# harp_rfid_reader_v1_0.net
KiCad netlist of a schematic drawn in EAGLE
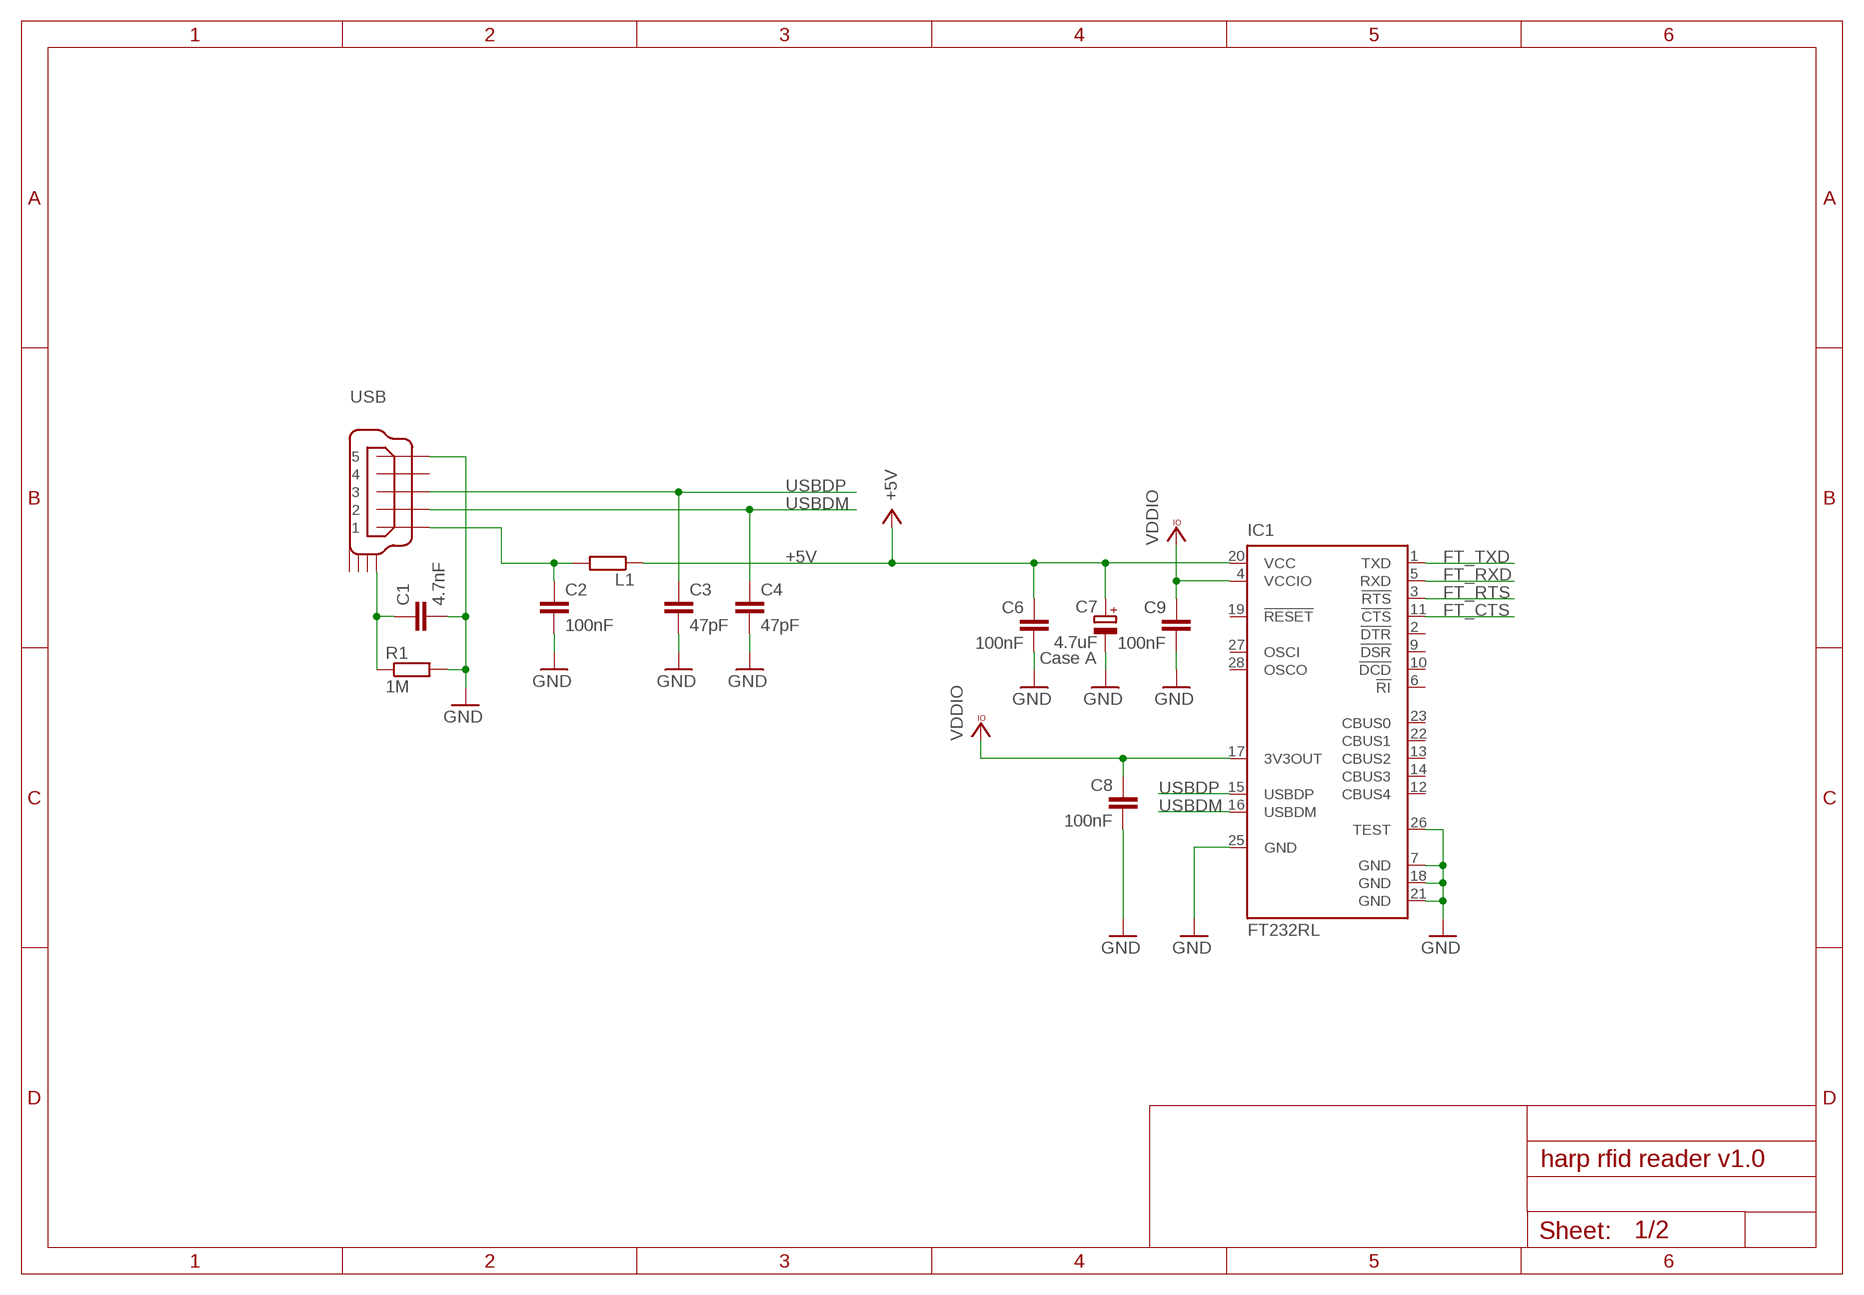
[diagram p0: schematic, sheet 1]
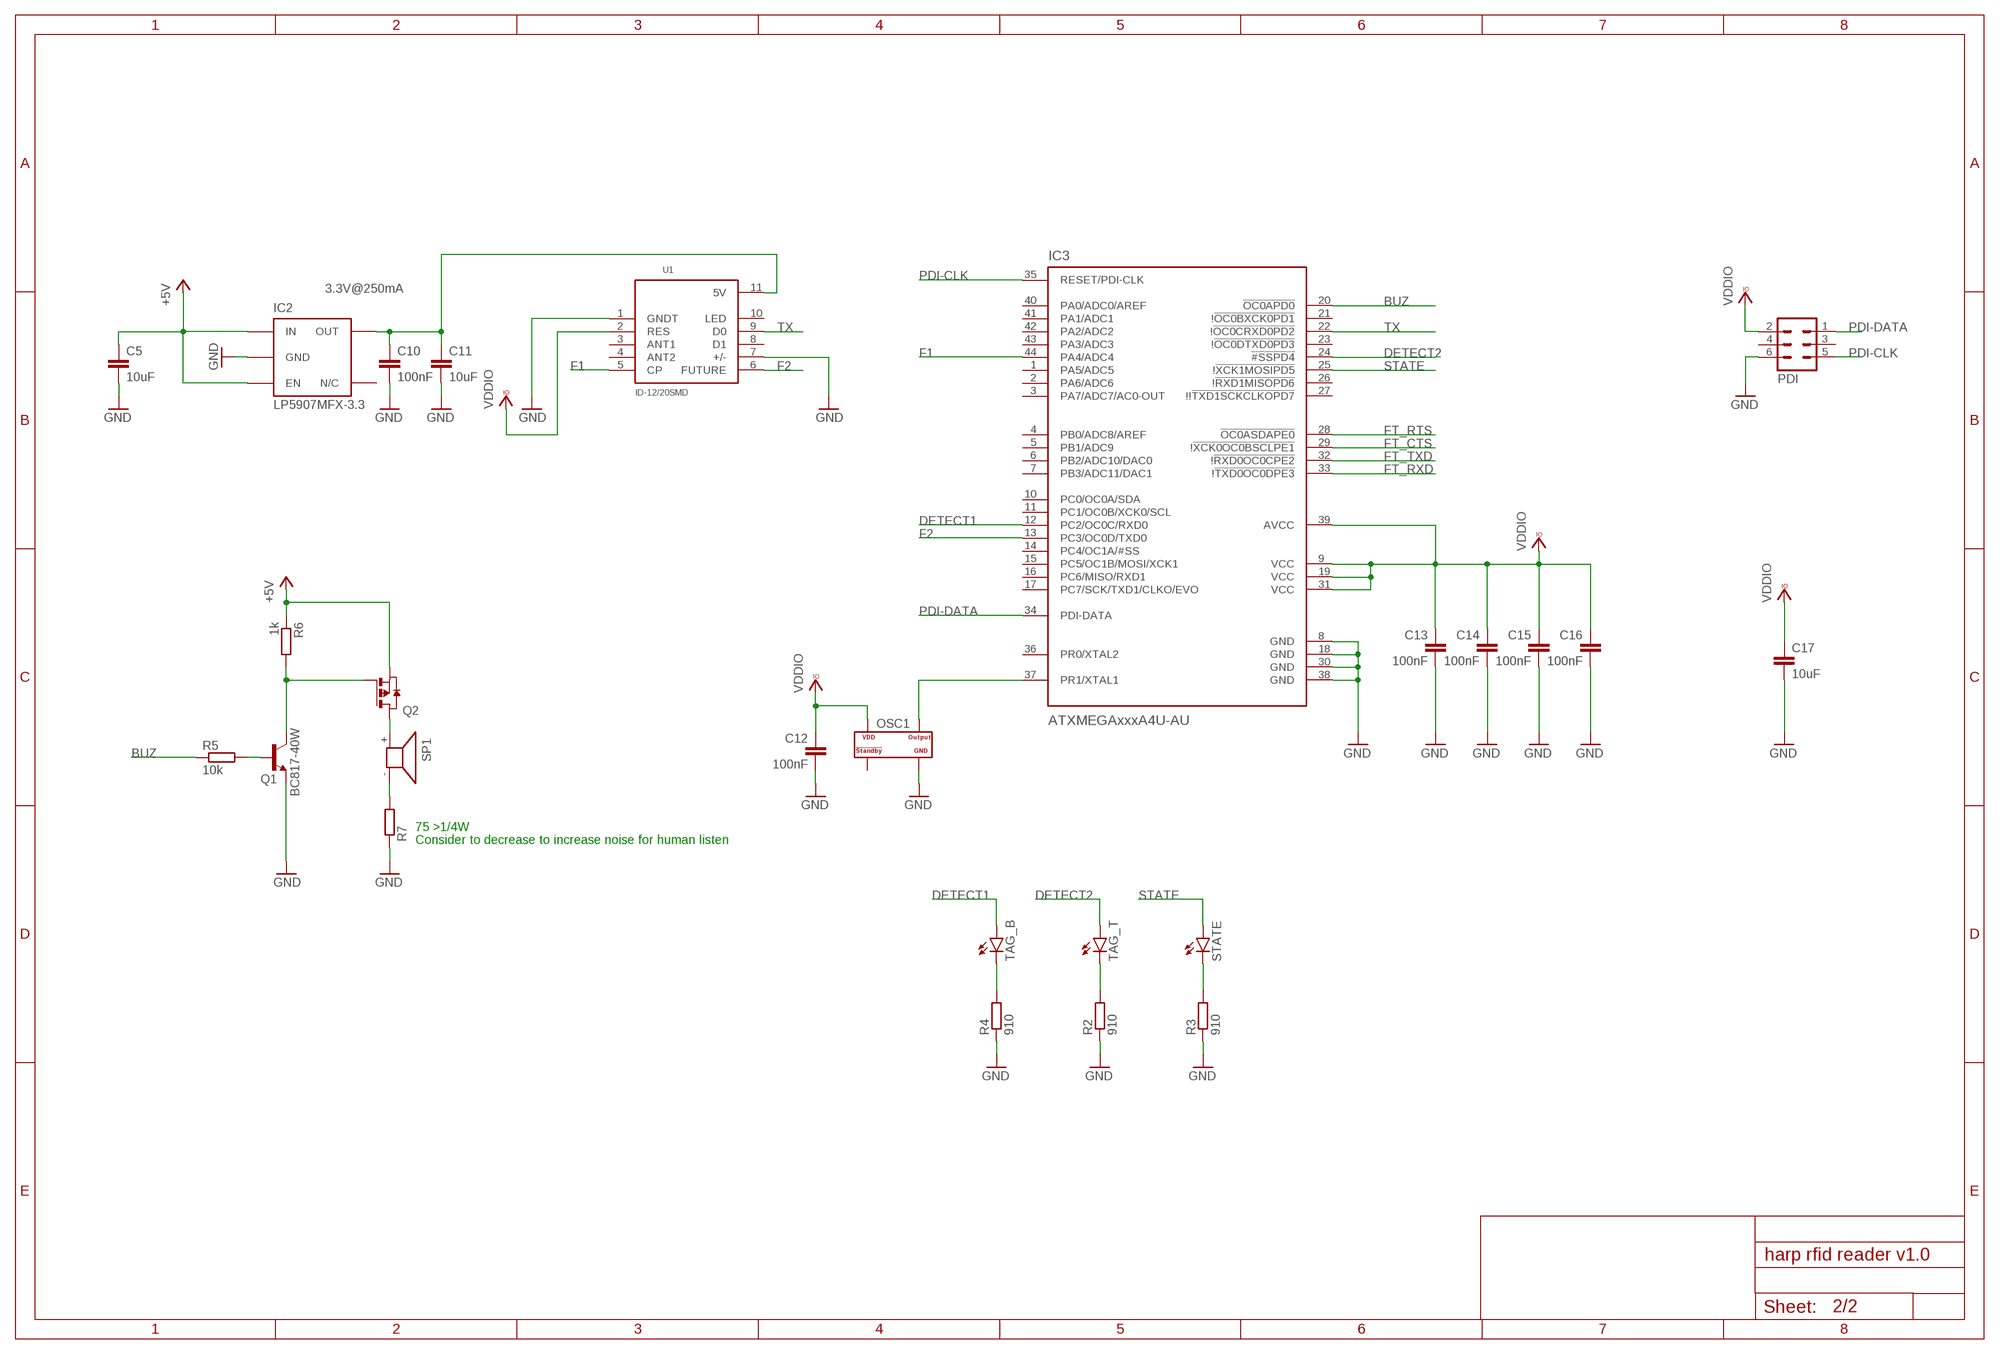
[diagram p1: schematic, sheet 2]

(export (version "E")
  (design (tool "Eeschema 10.0.6"))
  (components
    (comp (ref "C5")
      (value "10uF")
      (footprint "eagle-import:C0603")
      (libsource (lib "eagle-import") (part "C-EUC0603"))
    )
    (comp (ref "C10")
      (value "100nF")
      (footprint "eagle-import:C0402")
      (libsource (lib "eagle-import") (part "C-EUC0402"))
    )
    (comp (ref "C11")
      (value "10uF")
      (footprint "eagle-import:C0603")
      (libsource (lib "eagle-import") (part "C-EUC0603"))
    )
    (comp (ref "C12")
      (value "100nF")
      (footprint "eagle-import:C0402")
      (libsource (lib "eagle-import") (part "C-EUC0402"))
    )
    (comp (ref "C13")
      (value "100nF")
      (footprint "eagle-import:C0402")
      (libsource (lib "eagle-import") (part "C-EUC0402"))
    )
    (comp (ref "C14")
      (value "100nF")
      (footprint "eagle-import:C0402")
      (libsource (lib "eagle-import") (part "C-EUC0402"))
    )
    (comp (ref "C15")
      (value "100nF")
      (footprint "eagle-import:C0402")
      (libsource (lib "eagle-import") (part "C-EUC0402"))
    )
    (comp (ref "C16")
      (value "100nF")
      (footprint "eagle-import:C0402")
      (libsource (lib "eagle-import") (part "C-EUC0402"))
    )
    (comp (ref "C17")
      (value "10uF")
      (footprint "eagle-import:C0603")
      (libsource (lib "eagle-import") (part "C-EUC0603"))
    )
    (comp (ref "IC2")
      (value "LP5907MFX-3.3")
      (footprint "eagle-import:TSOT23-5")
      (libsource (lib "eagle-import") (part "TLV700XX"))
    )
    (comp (ref "IC3")
      (value "ATXMEGAxxxA4U-AU")
      (footprint "eagle-import:QFP80P1200X1200X120-44N")
      (libsource (lib "eagle-import") (part "AT-XMEGA-XXA4-AU"))
    )
    (comp (ref "OSC1")
      (value "CNP-MISCELLANEOUS_OSCILLATOR")
      (footprint "eagle-import:CNP-MISCELLANEOUS_OSCILLATOR_3.2X2.5")
      (libsource (lib "eagle-import") (part "CNP-MISCELLANEOUS_OSCILLATOR"))
    )
    (comp (ref "PDI")
      (value "MA03-2")
      (footprint "eagle-import:MA03-2")
      (libsource (lib "eagle-import") (part "MA03-2"))
    )
    (comp (ref "Q1")
      (value "BC817-40W")
      (footprint "eagle-import:SOT323-BEC")
      (libsource (lib "eagle-import") (part "BC817"))
    )
    (comp (ref "Q2")
      (value "PMOSSOT223")
      (footprint "eagle-import:SOT223")
      (libsource (lib "eagle-import") (part "PMOSSOT223"))
    )
    (comp (ref "R2")
      (value "910")
      (footprint "eagle-import:R0402")
      (libsource (lib "eagle-import") (part "rcl_334_R-EU_R0402"))
    )
    (comp (ref "R3")
      (value "910")
      (footprint "eagle-import:R0402")
      (libsource (lib "eagle-import") (part "rcl_334_R-EU_R0402"))
    )
    (comp (ref "R4")
      (value "910")
      (footprint "eagle-import:R0402")
      (libsource (lib "eagle-import") (part "rcl_334_R-EU_R0402"))
    )
    (comp (ref "R5")
      (value "10k")
      (footprint "eagle-import:R0402")
      (libsource (lib "eagle-import") (part "R-EU_R0402"))
    )
    (comp (ref "R6")
      (value "1k")
      (footprint "eagle-import:R0402")
      (libsource (lib "eagle-import") (part "R-EU_R0402"))
    )
    (comp (ref "R7")
      (value "75 >1/4W")
      (footprint "eagle-import:R0402")
      (libsource (lib "eagle-import") (part "R-EU_R0402"))
    )
    (comp (ref "SP1")
      (value "BUZZER-COIL_SMT-0540-S-R")
      (footprint "eagle-import:BUZZER-COIL_SMT-0540-S-R")
      (libsource (lib "eagle-import") (part "BUZZER-COIL_SMT-0540-S-R"))
    )
    (comp (ref "STATE")
      (value "LEDCHIP-LED0603")
      (footprint "eagle-import:CHIP-LED0603")
      (libsource (lib "eagle-import") (part "LEDCHIP-LED0603"))
    )
    (comp (ref "TAG_B")
      (value "LEDCHIP-LED0603")
      (footprint "eagle-import:CHIP-LED0603")
      (libsource (lib "eagle-import") (part "LEDCHIP-LED0603"))
    )
    (comp (ref "TAG_T")
      (value "LEDCHIP-LED0603")
      (footprint "eagle-import:CHIP-LED0603")
      (libsource (lib "eagle-import") (part "LEDCHIP-LED0603"))
    )
    (comp (ref "U1")
      (value "ID-12/20SMD")
      (footprint "eagle-import:ID-12_SMD")
      (libsource (lib "eagle-import") (part "ID-12/20SMD"))
    )
    (comp (ref "C1")
      (value "4.7nF")
      (footprint "eagle-import:C0402")
      (libsource (lib "eagle-import") (part "C-EUC0402"))
    )
    (comp (ref "C2")
      (value "100nF")
      (footprint "eagle-import:C0402")
      (libsource (lib "eagle-import") (part "C-EUC0402"))
    )
    (comp (ref "C3")
      (value "47pF")
      (footprint "eagle-import:C0402")
      (libsource (lib "eagle-import") (part "C-EUC0402"))
    )
    (comp (ref "C4")
      (value "47pF")
      (footprint "eagle-import:C0402")
      (libsource (lib "eagle-import") (part "C-EUC0402"))
    )
    (comp (ref "C6")
      (value "100nF")
      (footprint "eagle-import:C0402")
      (libsource (lib "eagle-import") (part "C-EUC0402"))
    )
    (comp (ref "C7")
      (value "4.7uF")
      (footprint "eagle-import:A_3216-18W")
      (libsource (lib "eagle-import") (part "CPOL-EUA/3216-18W"))
    )
    (comp (ref "C8")
      (value "100nF")
      (footprint "eagle-import:C0402")
      (libsource (lib "eagle-import") (part "C-EUC0402"))
    )
    (comp (ref "C9")
      (value "100nF")
      (footprint "eagle-import:C0402")
      (libsource (lib "eagle-import") (part "C-EUC0402"))
    )
    (comp (ref "IC1")
      (value "FT232RL")
      (footprint "eagle-import:SSOP28")
      (libsource (lib "eagle-import") (part "FT232RL"))
    )
    (comp (ref "L1")
      (value "???")
      (footprint "eagle-import:R0805")
      (libsource (lib "eagle-import") (part "R-EU_R0805"))
    )
    (comp (ref "R1")
      (value "1M")
      (footprint "eagle-import:R0402")
      (libsource (lib "eagle-import") (part "R-EU_R0402"))
    )
    (comp (ref "USB")
      (value "USB_MINI_B")
      (footprint "eagle-import:240-0002-1")
      (libsource (lib "eagle-import") (part "USB_MINI_B"))
    )
  )
  (nets
    (net (code "1") (name "+5V") (class "Default")
      (node (ref "C5") (pin "1") (pinfunction "1_1") (pintype "passive"))
      (node (ref "C6") (pin "1") (pinfunction "1_1") (pintype "passive"))
      (node (ref "C7") (pin "+") (pinfunction "+_+") (pintype "passive"))
      (node (ref "IC1") (pin "20") (pinfunction "VCC_20") (pintype "power_in"))
      (node (ref "IC2") (pin "1") (pinfunction "IN_1") (pintype "bidirectional"))
      (node (ref "IC2") (pin "3") (pinfunction "EN_3") (pintype "bidirectional"))
      (node (ref "L1") (pin "1") (pinfunction "1_1") (pintype "passive"))
      (node (ref "Q2") (pin "3") (pinfunction "S_3") (pintype "passive"))
      (node (ref "R6") (pin "1") (pinfunction "1_1") (pintype "passive"))
    )
    (net (code "2") (name "BUZ") (class "Default")
      (node (ref "IC3") (pin "20") (pinfunction "~{OC0APD0}_20") (pintype "bidirectional"))
      (node (ref "R5") (pin "1") (pinfunction "1_1") (pintype "passive"))
    )
    (net (code "3") (name "DETECT1") (class "Default")
      (node (ref "IC3") (pin "12") (pinfunction "PC2/OC0C/RXD0_12") (pintype "bidirectional"))
      (node (ref "TAG_B") (pin "A") (pinfunction "A_A") (pintype "passive"))
    )
    (net (code "4") (name "DETECT2") (class "Default")
      (node (ref "IC3") (pin "24") (pinfunction "~{#SSPD4}_24") (pintype "bidirectional"))
      (node (ref "TAG_T") (pin "A") (pinfunction "A_A") (pintype "passive"))
    )
    (net (code "5") (name "F1") (class "Default")
      (node (ref "IC3") (pin "44") (pinfunction "PA4/ADC4_44") (pintype "bidirectional"))
      (node (ref "U1") (pin "5") (pinfunction "CP_5") (pintype "bidirectional"))
    )
    (net (code "6") (name "F2") (class "Default")
      (node (ref "IC3") (pin "13") (pinfunction "PC3/OC0D/TXD0_13") (pintype "bidirectional"))
      (node (ref "U1") (pin "6") (pinfunction "FUTURE_6") (pintype "bidirectional"))
    )
    (net (code "7") (name "FT_CTS") (class "Default")
      (node (ref "IC1") (pin "11") (pinfunction "~{CTS}_11") (pintype "input"))
      (node (ref "IC3") (pin "29") (pinfunction "~XCK0OC0BSCLPE1_29") (pintype "bidirectional"))
    )
    (net (code "8") (name "FT_RTS") (class "Default")
      (node (ref "IC1") (pin "3") (pinfunction "~{RTS}_3") (pintype "output"))
      (node (ref "IC3") (pin "28") (pinfunction "~{OC0ASDAPE0}_28") (pintype "bidirectional"))
    )
    (net (code "9") (name "FT_RXD") (class "Default")
      (node (ref "IC1") (pin "5") (pinfunction "RXD_5") (pintype "input"))
      (node (ref "IC3") (pin "33") (pinfunction "~TXD0OC0DPE3_33") (pintype "bidirectional"))
    )
    (net (code "10") (name "FT_TXD") (class "Default")
      (node (ref "IC1") (pin "1") (pinfunction "TXD_1") (pintype "output"))
      (node (ref "IC3") (pin "32") (pinfunction "~RXD0OC0CPE2_32") (pintype "bidirectional"))
    )
    (net (code "11") (name "GND") (class "Default")
      (node (ref "C1") (pin "2") (pinfunction "2_2") (pintype "passive"))
      (node (ref "C10") (pin "2") (pinfunction "2_2") (pintype "passive"))
      (node (ref "C11") (pin "2") (pinfunction "2_2") (pintype "passive"))
      (node (ref "C12") (pin "2") (pinfunction "2_2") (pintype "passive"))
      (node (ref "C13") (pin "2") (pinfunction "2_2") (pintype "passive"))
      (node (ref "C14") (pin "2") (pinfunction "2_2") (pintype "passive"))
      (node (ref "C15") (pin "2") (pinfunction "2_2") (pintype "passive"))
      (node (ref "C16") (pin "2") (pinfunction "2_2") (pintype "passive"))
      (node (ref "C17") (pin "2") (pinfunction "2_2") (pintype "passive"))
      (node (ref "C2") (pin "2") (pinfunction "2_2") (pintype "passive"))
      (node (ref "C3") (pin "2") (pinfunction "2_2") (pintype "passive"))
      (node (ref "C4") (pin "2") (pinfunction "2_2") (pintype "passive"))
      (node (ref "C5") (pin "2") (pinfunction "2_2") (pintype "passive"))
      (node (ref "C6") (pin "2") (pinfunction "2_2") (pintype "passive"))
      (node (ref "C7") (pin "-") (pinfunction "-_-") (pintype "passive"))
      (node (ref "C8") (pin "2") (pinfunction "2_2") (pintype "passive"))
      (node (ref "C9") (pin "2") (pinfunction "2_2") (pintype "passive"))
      (node (ref "IC1") (pin "18") (pinfunction "GND_18") (pintype "power_in"))
      (node (ref "IC1") (pin "21") (pinfunction "GND_21") (pintype "power_in"))
      (node (ref "IC1") (pin "25") (pinfunction "GND_25") (pintype "power_in"))
      (node (ref "IC1") (pin "26") (pinfunction "TEST_26") (pintype "input"))
      (node (ref "IC1") (pin "7") (pinfunction "GND_7") (pintype "power_in"))
      (node (ref "IC2") (pin "2") (pinfunction "GND_2") (pintype "bidirectional"))
      (node (ref "IC3") (pin "18") (pinfunction "GND_18") (pintype "power_in"))
      (node (ref "IC3") (pin "30") (pinfunction "GND_30") (pintype "power_in"))
      (node (ref "IC3") (pin "38") (pinfunction "GND_38") (pintype "power_in"))
      (node (ref "IC3") (pin "8") (pinfunction "GND_8") (pintype "power_in"))
      (node (ref "OSC1") (pin "P$2") (pinfunction "GND_P$2") (pintype "passive"))
      (node (ref "PDI") (pin "6") (pinfunction "6_6") (pintype "passive"))
      (node (ref "Q1") (pin "E") (pinfunction "E_E") (pintype "passive"))
      (node (ref "R1") (pin "2") (pinfunction "2_2") (pintype "passive"))
      (node (ref "R2") (pin "1") (pinfunction "1_1") (pintype "passive"))
      (node (ref "R3") (pin "1") (pinfunction "1_1") (pintype "passive"))
      (node (ref "R4") (pin "1") (pinfunction "1_1") (pintype "passive"))
      (node (ref "R7") (pin "1") (pinfunction "1_1") (pintype "passive"))
      (node (ref "U1") (pin "1") (pinfunction "GNDT_1") (pintype "bidirectional"))
      (node (ref "U1") (pin "7") (pinfunction "+/-_7") (pintype "bidirectional"))
      (node (ref "USB") (pin "P$5") (pinfunction "5_P$5") (pintype "bidirectional"))
    )
    (net (code "12") (name "Net-(IC2-OUT)") (class "Default")
      (node (ref "C10") (pin "1") (pinfunction "1_1") (pintype "passive"))
      (node (ref "C11") (pin "1") (pinfunction "1_1") (pintype "passive"))
      (node (ref "IC2") (pin "5") (pinfunction "OUT_5") (pintype "bidirectional"))
      (node (ref "U1") (pin "11") (pinfunction "5V_11") (pintype "bidirectional"))
    )
    (net (code "13") (name "Net-(IC3-PR1{slash}XTAL1)") (class "Default")
      (node (ref "IC3") (pin "37") (pinfunction "PR1/XTAL1_37") (pintype "bidirectional"))
      (node (ref "OSC1") (pin "P$3") (pinfunction "OUTPUT_P$3") (pintype "passive"))
    )
    (net (code "14") (name "Net-(Q1-PadB)") (class "Default")
      (node (ref "Q1") (pin "B") (pinfunction "B_B") (pintype "passive"))
      (node (ref "R5") (pin "2") (pinfunction "2_2") (pintype "passive"))
    )
    (net (code "15") (name "Net-(Q2-D-Pad2)") (class "Default")
      (node (ref "Q2") (pin "2") (pinfunction "D_2") (pintype "passive"))
      (node (ref "Q2") (pin "4") (pinfunction "D_4") (pintype "passive"))
      (node (ref "SP1") (pin "+") (pinfunction "+_+") (pintype "passive"))
    )
    (net (code "16") (name "Net-(Q2-G)") (class "Default")
      (node (ref "Q1") (pin "C") (pinfunction "C_C") (pintype "passive"))
      (node (ref "Q2") (pin "1") (pinfunction "G_1") (pintype "passive"))
      (node (ref "R6") (pin "2") (pinfunction "2_2") (pintype "passive"))
    )
    (net (code "17") (name "Net-(R2-Pad2)") (class "Default")
      (node (ref "R2") (pin "2") (pinfunction "2_2") (pintype "passive"))
      (node (ref "TAG_T") (pin "C") (pinfunction "C_C") (pintype "passive"))
    )
    (net (code "18") (name "Net-(R3-Pad2)") (class "Default")
      (node (ref "R3") (pin "2") (pinfunction "2_2") (pintype "passive"))
      (node (ref "STATE") (pin "C") (pinfunction "C_C") (pintype "passive"))
    )
    (net (code "19") (name "Net-(R4-Pad2)") (class "Default")
      (node (ref "R4") (pin "2") (pinfunction "2_2") (pintype "passive"))
      (node (ref "TAG_B") (pin "C") (pinfunction "C_C") (pintype "passive"))
    )
    (net (code "20") (name "Net-(R7-Pad2)") (class "Default")
      (node (ref "R7") (pin "2") (pinfunction "2_2") (pintype "passive"))
      (node (ref "SP1") (pin "-") (pinfunction "-_-") (pintype "passive"))
    )
    (net (code "21") (name "Net-(USB-1)") (class "Default")
      (node (ref "C2") (pin "1") (pinfunction "1_1") (pintype "passive"))
      (node (ref "L1") (pin "2") (pinfunction "2_2") (pintype "passive"))
      (node (ref "USB") (pin "P$1") (pinfunction "1_P$1") (pintype "bidirectional"))
    )
    (net (code "22") (name "Net-(USB-P$1)") (class "Default")
      (node (ref "C1") (pin "1") (pinfunction "1_1") (pintype "passive"))
      (node (ref "R1") (pin "1") (pinfunction "1_1") (pintype "passive"))
      (node (ref "USB") (pin "SHIELD_1") (pinfunction "P$1_SHIELD_1") (pintype "bidirectional"))
    )
    (net (code "23") (name "PDI-CLK") (class "Default")
      (node (ref "IC3") (pin "35") (pinfunction "RESET/PDI-CLK_35") (pintype "input"))
      (node (ref "PDI") (pin "5") (pinfunction "5_5") (pintype "passive"))
    )
    (net (code "24") (name "PDI-DATA") (class "Default")
      (node (ref "IC3") (pin "34") (pinfunction "PDI-DATA_34") (pintype "bidirectional"))
      (node (ref "PDI") (pin "1") (pinfunction "1_1") (pintype "passive"))
    )
    (net (code "25") (name "STATE") (class "Default")
      (node (ref "IC3") (pin "25") (pinfunction "~XCK1MOSIPD5_25") (pintype "bidirectional"))
      (node (ref "STATE") (pin "A") (pinfunction "A_A") (pintype "passive"))
    )
    (net (code "26") (name "TX") (class "Default")
      (node (ref "IC3") (pin "22") (pinfunction "~OC0CRXD0PD2_22") (pintype "bidirectional"))
      (node (ref "U1") (pin "9") (pinfunction "D0_9") (pintype "bidirectional"))
    )
    (net (code "27") (name "USBDM") (class "Default")
      (node (ref "C4") (pin "1") (pinfunction "1_1") (pintype "passive"))
      (node (ref "IC1") (pin "16") (pinfunction "USBDM_16") (pintype "bidirectional"))
      (node (ref "USB") (pin "P$2") (pinfunction "2_P$2") (pintype "bidirectional"))
    )
    (net (code "28") (name "USBDP") (class "Default")
      (node (ref "C3") (pin "1") (pinfunction "1_1") (pintype "passive"))
      (node (ref "IC1") (pin "15") (pinfunction "USBDP_15") (pintype "bidirectional"))
      (node (ref "USB") (pin "P$3") (pinfunction "3_P$3") (pintype "bidirectional"))
    )
    (net (code "29") (name "VCCIO") (class "Default")
      (node (ref "C12") (pin "1") (pinfunction "1_1") (pintype "passive"))
      (node (ref "C13") (pin "1") (pinfunction "1_1") (pintype "passive"))
      (node (ref "C14") (pin "1") (pinfunction "1_1") (pintype "passive"))
      (node (ref "C15") (pin "1") (pinfunction "1_1") (pintype "passive"))
      (node (ref "C16") (pin "1") (pinfunction "1_1") (pintype "passive"))
      (node (ref "C17") (pin "1") (pinfunction "1_1") (pintype "passive"))
      (node (ref "C8") (pin "1") (pinfunction "1_1") (pintype "passive"))
      (node (ref "C9") (pin "1") (pinfunction "1_1") (pintype "passive"))
      (node (ref "IC1") (pin "17") (pinfunction "3V3OUT_17") (pintype "output"))
      (node (ref "IC1") (pin "4") (pinfunction "VCCIO_4") (pintype "power_in"))
      (node (ref "IC3") (pin "19") (pinfunction "VCC_19") (pintype "power_in"))
      (node (ref "IC3") (pin "31") (pinfunction "VCC_31") (pintype "power_in"))
      (node (ref "IC3") (pin "39") (pinfunction "AVCC_39") (pintype "power_in"))
      (node (ref "IC3") (pin "9") (pinfunction "VCC_9") (pintype "power_in"))
      (node (ref "OSC1") (pin "P$4") (pinfunction "VDD_P$4") (pintype "passive"))
      (node (ref "PDI") (pin "2") (pinfunction "2_2") (pintype "passive"))
      (node (ref "U1") (pin "2") (pinfunction "RES_2") (pintype "bidirectional"))
    )
    (net (code "30") (name "unconnected-(IC1-CBUS0-Pad23)") (class "Default")
      (node (ref "IC1") (pin "23") (pinfunction "CBUS0_23") (pintype "bidirectional"))
    )
    (net (code "31") (name "unconnected-(IC1-CBUS1-Pad22)") (class "Default")
      (node (ref "IC1") (pin "22") (pinfunction "CBUS1_22") (pintype "bidirectional"))
    )
    (net (code "32") (name "unconnected-(IC1-CBUS2-Pad13)") (class "Default")
      (node (ref "IC1") (pin "13") (pinfunction "CBUS2_13") (pintype "bidirectional"))
    )
    (net (code "33") (name "unconnected-(IC1-CBUS3-Pad14)") (class "Default")
      (node (ref "IC1") (pin "14") (pinfunction "CBUS3_14") (pintype "bidirectional"))
    )
    (net (code "34") (name "unconnected-(IC1-CBUS4-Pad12)") (class "Default")
      (node (ref "IC1") (pin "12") (pinfunction "CBUS4_12") (pintype "bidirectional"))
    )
    (net (code "35") (name "unconnected-(IC1-OSCI-Pad27)") (class "Default")
      (node (ref "IC1") (pin "27") (pinfunction "OSCI_27") (pintype "input"))
    )
    (net (code "36") (name "unconnected-(IC1-OSCO-Pad28)") (class "Default")
      (node (ref "IC1") (pin "28") (pinfunction "OSCO_28") (pintype "output"))
    )
    (net (code "37") (name "unconnected-(IC1-~{DCD}-Pad10)") (class "Default")
      (node (ref "IC1") (pin "10") (pinfunction "~{DCD}_10") (pintype "input"))
    )
    (net (code "38") (name "unconnected-(IC1-~{DSR}-Pad9)") (class "Default")
      (node (ref "IC1") (pin "9") (pinfunction "~{DSR}_9") (pintype "input"))
    )
    (net (code "39") (name "unconnected-(IC1-~{DTR}-Pad2)") (class "Default")
      (node (ref "IC1") (pin "2") (pinfunction "~{DTR}_2") (pintype "output"))
    )
    (net (code "40") (name "unconnected-(IC1-~{RESET}-Pad19)") (class "Default")
      (node (ref "IC1") (pin "19") (pinfunction "~{RESET}_19") (pintype "input"))
    )
    (net (code "41") (name "unconnected-(IC1-~{RI}-Pad6)") (class "Default")
      (node (ref "IC1") (pin "6") (pinfunction "~{RI}_6") (pintype "input"))
    )
    (net (code "42") (name "unconnected-(IC2-N{slash}C-Pad4)") (class "Default")
      (node (ref "IC2") (pin "4") (pinfunction "N/C_4") (pintype "bidirectional"))
    )
    (net (code "43") (name "unconnected-(IC3-PA0{slash}ADC0{slash}AREF-Pad40)") (class "Default")
      (node (ref "IC3") (pin "40") (pinfunction "PA0/ADC0/AREF_40") (pintype "bidirectional"))
    )
    (net (code "44") (name "unconnected-(IC3-PA1{slash}ADC1-Pad41)") (class "Default")
      (node (ref "IC3") (pin "41") (pinfunction "PA1/ADC1_41") (pintype "bidirectional"))
    )
    (net (code "45") (name "unconnected-(IC3-PA2{slash}ADC2-Pad42)") (class "Default")
      (node (ref "IC3") (pin "42") (pinfunction "PA2/ADC2_42") (pintype "bidirectional"))
    )
    (net (code "46") (name "unconnected-(IC3-PA3{slash}ADC3-Pad43)") (class "Default")
      (node (ref "IC3") (pin "43") (pinfunction "PA3/ADC3_43") (pintype "bidirectional"))
    )
    (net (code "47") (name "unconnected-(IC3-PA5{slash}ADC5-Pad1)") (class "Default")
      (node (ref "IC3") (pin "1") (pinfunction "PA5/ADC5_1") (pintype "bidirectional"))
    )
    (net (code "48") (name "unconnected-(IC3-PA6{slash}ADC6-Pad2)") (class "Default")
      (node (ref "IC3") (pin "2") (pinfunction "PA6/ADC6_2") (pintype "bidirectional"))
    )
    (net (code "49") (name "unconnected-(IC3-PA7{slash}ADC7{slash}AC0-OUT-Pad3)") (class "Default")
      (node (ref "IC3") (pin "3") (pinfunction "PA7/ADC7/AC0-OUT_3") (pintype "bidirectional"))
    )
    (net (code "50") (name "unconnected-(IC3-PB0{slash}ADC8{slash}AREF-Pad4)") (class "Default")
      (node (ref "IC3") (pin "4") (pinfunction "PB0/ADC8/AREF_4") (pintype "bidirectional"))
    )
    (net (code "51") (name "unconnected-(IC3-PB1{slash}ADC9-Pad5)") (class "Default")
      (node (ref "IC3") (pin "5") (pinfunction "PB1/ADC9_5") (pintype "bidirectional"))
    )
    (net (code "52") (name "unconnected-(IC3-PB2{slash}ADC10{slash}DAC0-Pad6)") (class "Default")
      (node (ref "IC3") (pin "6") (pinfunction "PB2/ADC10/DAC0_6") (pintype "bidirectional"))
    )
    (net (code "53") (name "unconnected-(IC3-PB3{slash}ADC11{slash}DAC1-Pad7)") (class "Default")
      (node (ref "IC3") (pin "7") (pinfunction "PB3/ADC11/DAC1_7") (pintype "bidirectional"))
    )
    (net (code "54") (name "unconnected-(IC3-PC0{slash}OC0A{slash}SDA-Pad10)") (class "Default")
      (node (ref "IC3") (pin "10") (pinfunction "PC0/OC0A/SDA_10") (pintype "bidirectional"))
    )
    (net (code "55") (name "unconnected-(IC3-PC1{slash}OC0B{slash}XCK0{slash}SCL-Pad11)") (class "Default")
      (node (ref "IC3") (pin "11") (pinfunction "PC1/OC0B/XCK0/SCL_11") (pintype "bidirectional"))
    )
    (net (code "56") (name "unconnected-(IC3-PC4{slash}OC1A{slash}#SS-Pad14)") (class "Default")
      (node (ref "IC3") (pin "14") (pinfunction "PC4/OC1A/#SS_14") (pintype "bidirectional"))
    )
    (net (code "57") (name "unconnected-(IC3-PC5{slash}OC1B{slash}MOSI{slash}XCK1-Pad15)") (class "Default")
      (node (ref "IC3") (pin "15") (pinfunction "PC5/OC1B/MOSI/XCK1_15") (pintype "bidirectional"))
    )
    (net (code "58") (name "unconnected-(IC3-PC6{slash}MISO{slash}RXD1-Pad16)") (class "Default")
      (node (ref "IC3") (pin "16") (pinfunction "PC6/MISO/RXD1_16") (pintype "bidirectional"))
    )
    (net (code "59") (name "unconnected-(IC3-PC7{slash}SCK{slash}TXD1{slash}CLKO{slash}EVO-Pad17)") (class "Default")
      (node (ref "IC3") (pin "17") (pinfunction "PC7/SCK/TXD1/CLKO/EVO_17") (pintype "bidirectional"))
    )
    (net (code "60") (name "unconnected-(IC3-PR0{slash}XTAL2-Pad36)") (class "Default")
      (node (ref "IC3") (pin "36") (pinfunction "PR0/XTAL2_36") (pintype "bidirectional"))
    )
    (net (code "61") (name "unconnected-(IC3-~OC0BXCK0PD1-Pad21)") (class "Default")
      (node (ref "IC3") (pin "21") (pinfunction "~OC0BXCK0PD1_21") (pintype "bidirectional"))
    )
    (net (code "62") (name "unconnected-(IC3-~OC0DTXD0PD3-Pad23)") (class "Default")
      (node (ref "IC3") (pin "23") (pinfunction "~OC0DTXD0PD3_23") (pintype "bidirectional"))
    )
    (net (code "63") (name "unconnected-(IC3-~RXD1MISOPD6-Pad26)") (class "Default")
      (node (ref "IC3") (pin "26") (pinfunction "~RXD1MISOPD6_26") (pintype "bidirectional"))
    )
    (net (code "64") (name "unconnected-(IC3-~~{TXD1SCKCLKOPD7}-Pad27)") (class "Default")
      (node (ref "IC3") (pin "27") (pinfunction "~~{TXD1SCKCLKOPD7}_27") (pintype "bidirectional"))
    )
    (net (code "65") (name "unconnected-(OSC1-STANDBY#-PadP$1)") (class "Default")
      (node (ref "OSC1") (pin "P$1") (pinfunction "STANDBY#_P$1") (pintype "passive"))
    )
    (net (code "66") (name "unconnected-(PDI-Pad3)") (class "Default")
      (node (ref "PDI") (pin "3") (pinfunction "3_3") (pintype "passive"))
    )
    (net (code "67") (name "unconnected-(PDI-Pad4)") (class "Default")
      (node (ref "PDI") (pin "4") (pinfunction "4_4") (pintype "passive"))
    )
    (net (code "68") (name "unconnected-(U1-ANT1-Pad3)") (class "Default")
      (node (ref "U1") (pin "3") (pinfunction "ANT1_3") (pintype "bidirectional"))
    )
    (net (code "69") (name "unconnected-(U1-ANT2-Pad4)") (class "Default")
      (node (ref "U1") (pin "4") (pinfunction "ANT2_4") (pintype "bidirectional"))
    )
    (net (code "70") (name "unconnected-(U1-D1-Pad8)") (class "Default")
      (node (ref "U1") (pin "8") (pinfunction "D1_8") (pintype "bidirectional"))
    )
    (net (code "71") (name "unconnected-(U1-LED-Pad10)") (class "Default")
      (node (ref "U1") (pin "10") (pinfunction "LED_10") (pintype "bidirectional"))
    )
    (net (code "72") (name "unconnected-(USB-4-PadP$4)") (class "Default")
      (node (ref "USB") (pin "P$4") (pinfunction "4_P$4") (pintype "bidirectional"))
    )
    (net (code "73") (name "unconnected-(USB-P$2-PadSHIELD_2)") (class "Default")
      (node (ref "USB") (pin "SHIELD_2") (pinfunction "P$2_SHIELD_2") (pintype "bidirectional"))
    )
    (net (code "74") (name "unconnected-(USB-P$3-PadSHIELD_3)") (class "Default")
      (node (ref "USB") (pin "SHIELD_3") (pinfunction "P$3_SHIELD_3") (pintype "bidirectional"))
    )
    (net (code "75") (name "unconnected-(USB-P$4-PadSHIELD_4)") (class "Default")
      (node (ref "USB") (pin "SHIELD_4") (pinfunction "P$4_SHIELD_4") (pintype "bidirectional"))
    )
  )
)
